# PDB.net
KiCad netlist of a schematic drawn in EAGLE
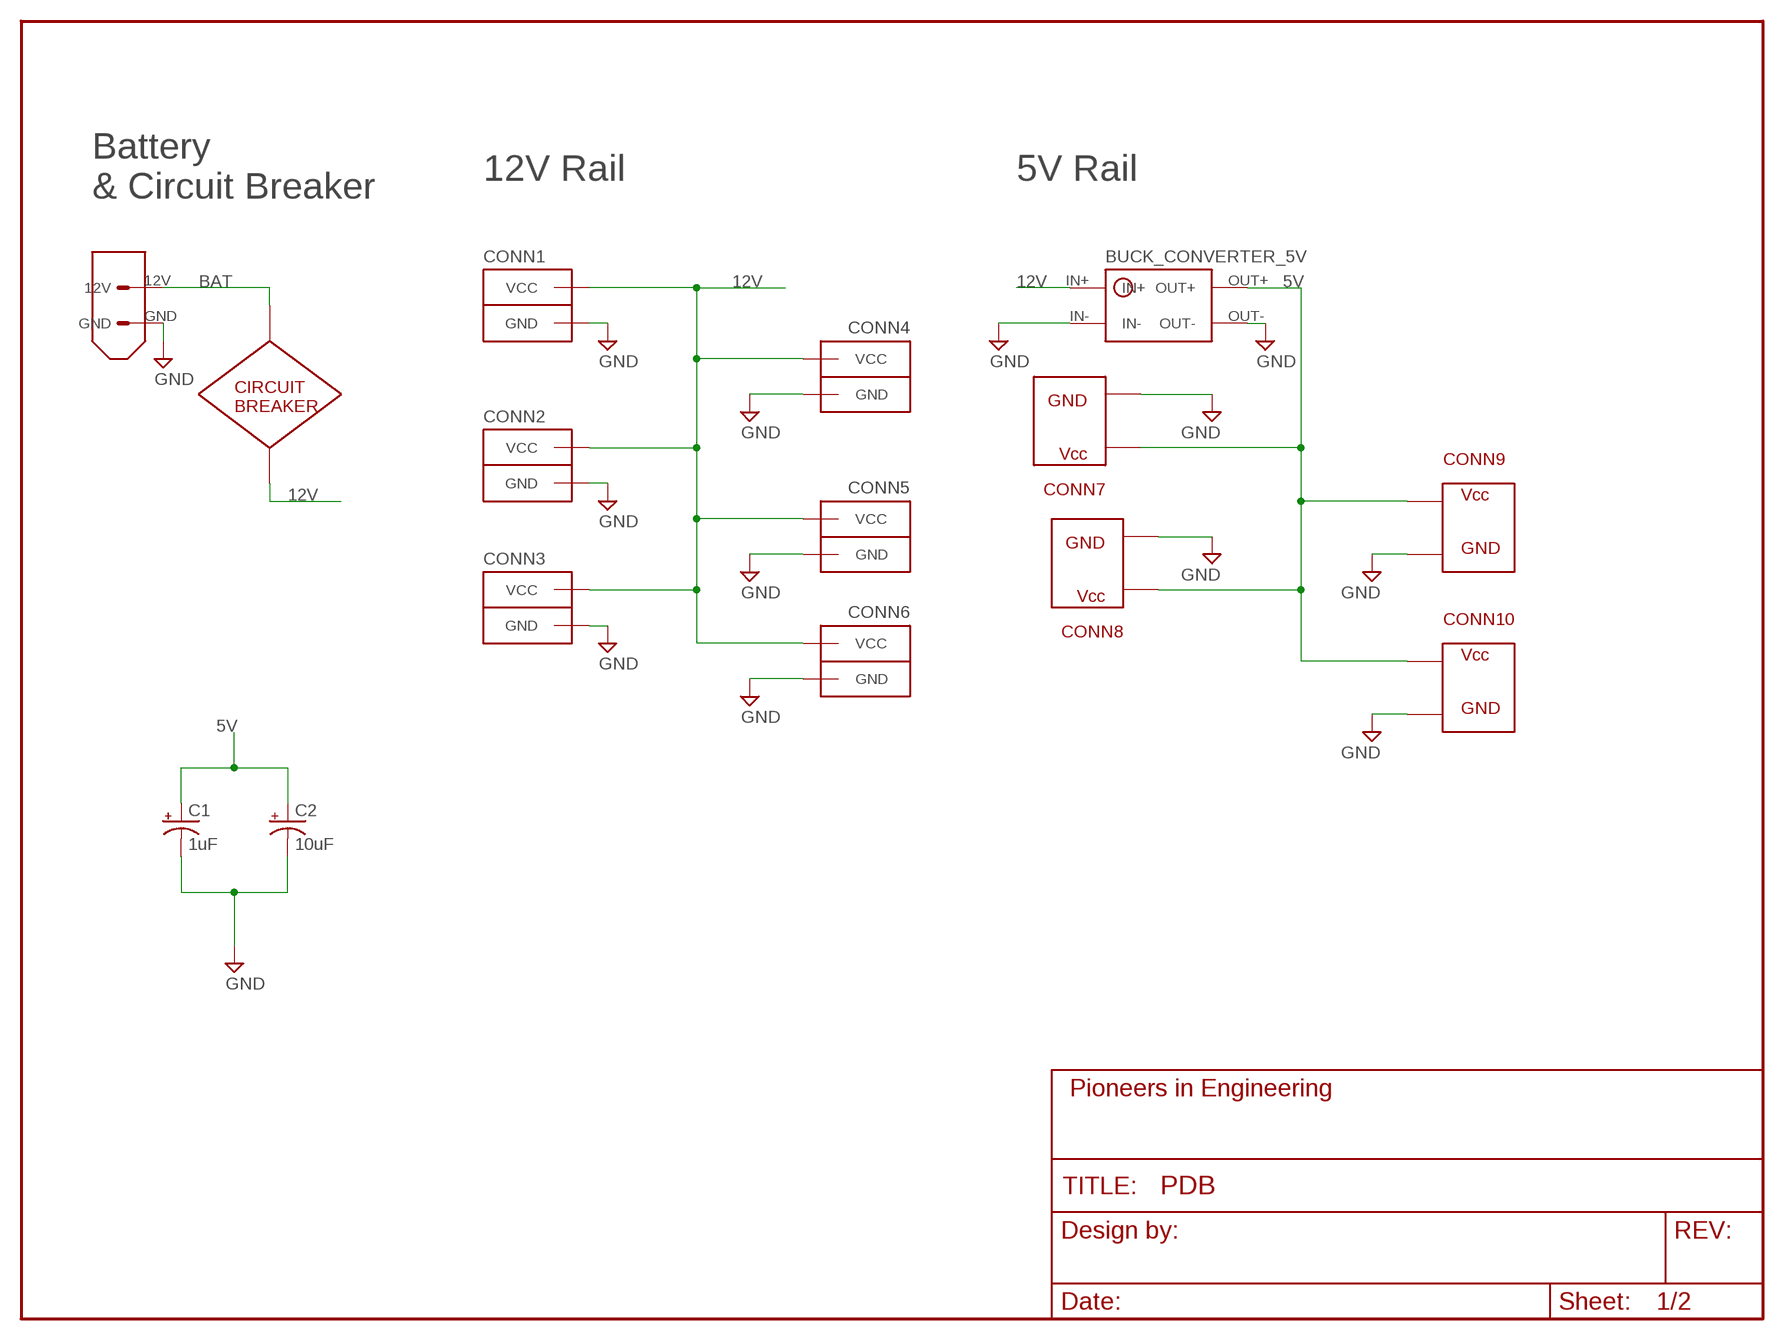
[diagram p0: schematic, sheet 1]
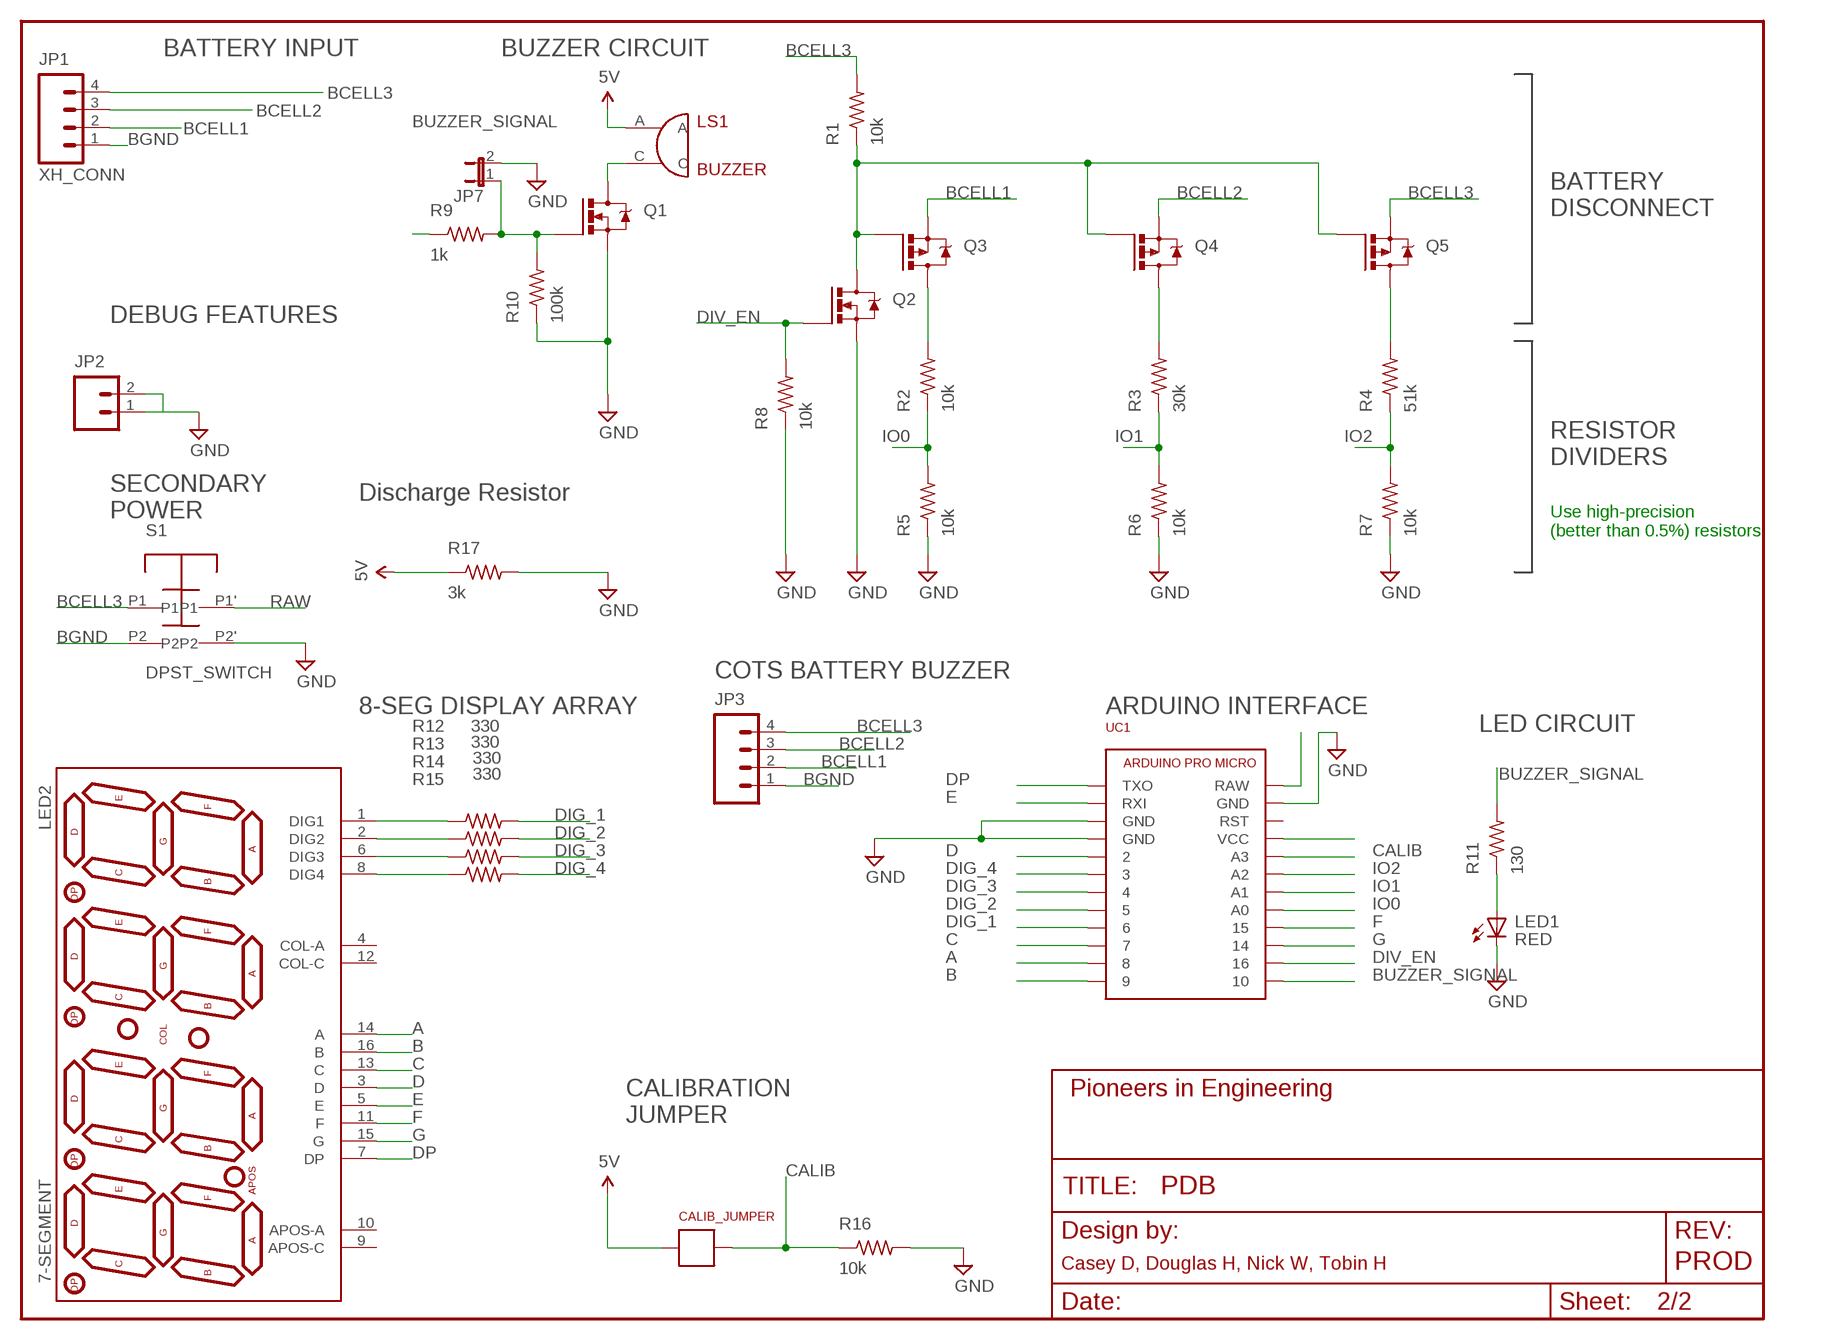
[diagram p1: schematic, sheet 2]

(export (version "E")
  (design (tool "Eeschema 10.0.6"))
  (components
    (comp (ref "CALIB_JUMPER")
      (value "JUMPER")
      (footprint "eagle-import:JUMPER")
      (fields
        (field (name "DISTRIBUTOR_PART_NUMBER") "952-2262-ND")
        (field (name "MANUFACTURER") "Harwin. Inc")
        (field (name "MANUFACTURER_PART_NUMBER") "M20-9990246")
      )
      (libsource (lib "eagle-import") (part "JUMPER"))
    )
    (comp (ref "JP1")
      (value "XH_CONN")
      (footprint "eagle-import:XH_CONNECTOR_4POS_2.5MM")
      (libsource (lib "eagle-import") (part "XH_CONNECTOR_4POS"))
    )
    (comp (ref "JP2")
      (value "M02PTH")
      (footprint "eagle-import:1X02")
      (libsource (lib "eagle-import") (part "M02PTH"))
    )
    (comp (ref "JP3")
      (value "M04PTH")
      (footprint "eagle-import:1X04")
      (libsource (lib "eagle-import") (part "M04PTH"))
    )
    (comp (ref "JP7")
      (value "JP1E")
      (footprint "eagle-import:JP1")
      (libsource (lib "eagle-import") (part "JP1E"))
    )
    (comp (ref "LED1")
      (value "RED")
      (footprint "eagle-import:LED-0805")
      (libsource (lib "eagle-import") (part "LED0805"))
    )
    (comp (ref "LED2")
      (value "7-SEGMENT")
      (footprint "eagle-import:7-SEGMENT-4DIGIT-YOUNGSUN")
      (libsource (lib "eagle-import") (part "7-SEGMENT-4DIGIT-YOUNGSUN"))
    )
    (comp (ref "LS1")
      (value "BUZZER")
      (footprint "eagle-import:BUZZER_MAGNETIC_5V_12MM_RADIAL")
      (libsource (lib "eagle-import") (part "BUZZER"))
    )
    (comp (ref "Q1")
      (value "NMOS")
      (footprint "eagle-import:SOT23-3")
      (libsource (lib "eagle-import") (part "N-CHANNEL-MOSFETSOT23-3"))
    )
    (comp (ref "Q2")
      (value "IRFML8244")
      (footprint "eagle-import:SOT23-3")
      (libsource (lib "eagle-import") (part "N-CHANNEL-MOSFETSOT23-3"))
    )
    (comp (ref "Q3")
      (value "PMOS")
      (footprint "eagle-import:SOT23-3")
      (libsource (lib "eagle-import") (part "P-CHANNEL-MOSFETSOT23-3"))
    )
    (comp (ref "Q4")
      (value "PMOS")
      (footprint "eagle-import:SOT23-3")
      (libsource (lib "eagle-import") (part "P-CHANNEL-MOSFETSOT23-3"))
    )
    (comp (ref "Q5")
      (value "PMOS")
      (footprint "eagle-import:SOT23-3")
      (libsource (lib "eagle-import") (part "P-CHANNEL-MOSFETSOT23-3"))
    )
    (comp (ref "R1")
      (value "10k")
      (footprint "eagle-import:R0603")
      (fields (field (name "MANUFACTURER") "Rohm Semiconductor"))
      (libsource (lib "eagle-import") (part "R-US_R0603"))
    )
    (comp (ref "R2")
      (value "10k")
      (footprint "eagle-import:R0603")
      (fields (field (name "MANUFACTURER") "Rohm Semiconductor"))
      (libsource (lib "eagle-import") (part "R-US_R0603"))
    )
    (comp (ref "R3")
      (value "30k")
      (footprint "eagle-import:R0603")
      (fields (field (name "MANUFACTURER") "Rohm Semiconductor"))
      (libsource (lib "eagle-import") (part "R-US_R0603"))
    )
    (comp (ref "R4")
      (value "51k")
      (footprint "eagle-import:R0603")
      (fields (field (name "MANUFACTURER") "Rohm Semiconductor"))
      (libsource (lib "eagle-import") (part "R-US_R0603"))
    )
    (comp (ref "R5")
      (value "10k")
      (footprint "eagle-import:R0603")
      (fields (field (name "MANUFACTURER") "Rohm Semiconductor"))
      (libsource (lib "eagle-import") (part "R-US_R0603"))
    )
    (comp (ref "R6")
      (value "10k")
      (footprint "eagle-import:R0603")
      (fields (field (name "MANUFACTURER") "Rohm Semiconductor"))
      (libsource (lib "eagle-import") (part "R-US_R0603"))
    )
    (comp (ref "R7")
      (value "10k")
      (footprint "eagle-import:R0603")
      (fields (field (name "MANUFACTURER") "Rohm Semiconductor"))
      (libsource (lib "eagle-import") (part "R-US_R0603"))
    )
    (comp (ref "R8")
      (value "10k")
      (footprint "eagle-import:R0603")
      (fields (field (name "MANUFACTURER") "Rohm Semiconductor"))
      (libsource (lib "eagle-import") (part "R-US_R0603"))
    )
    (comp (ref "R9")
      (value "1k")
      (footprint "eagle-import:R0603")
      (fields (field (name "MANUFACTURER") "Rohm Semiconductor"))
      (libsource (lib "eagle-import") (part "R-US_R0603"))
    )
    (comp (ref "R10")
      (value "100k")
      (footprint "eagle-import:R0603")
      (fields (field (name "MANUFACTURER") "Rohm Semiconductor"))
      (libsource (lib "eagle-import") (part "R-US_R0603"))
    )
    (comp (ref "R11")
      (value "130")
      (footprint "eagle-import:R0603")
      (fields (field (name "MANUFACTURER") "Rohm Semiconductor"))
      (libsource (lib "eagle-import") (part "R-US_R0603"))
    )
    (comp (ref "R12")
      (value "330")
      (footprint "eagle-import:R0603")
      (fields (field (name "MANUFACTURER") "Rohm Semiconductor"))
      (libsource (lib "eagle-import") (part "R-US_R0603"))
    )
    (comp (ref "R13")
      (value "330")
      (footprint "eagle-import:R0603")
      (fields (field (name "MANUFACTURER") "Rohm Semiconductor"))
      (libsource (lib "eagle-import") (part "R-US_R0603"))
    )
    (comp (ref "R14")
      (value "330")
      (footprint "eagle-import:R0603")
      (fields (field (name "MANUFACTURER") "Rohm Semiconductor"))
      (libsource (lib "eagle-import") (part "R-US_R0603"))
    )
    (comp (ref "R15")
      (value "330")
      (footprint "eagle-import:R0603")
      (fields (field (name "MANUFACTURER") "Rohm Semiconductor"))
      (libsource (lib "eagle-import") (part "R-US_R0603"))
    )
    (comp (ref "R16")
      (value "10k")
      (footprint "eagle-import:R0603")
      (fields (field (name "MANUFACTURER") "Rohm Semiconductor"))
      (libsource (lib "eagle-import") (part "R-US_R0603"))
    )
    (comp (ref "R17")
      (value "3k")
      (footprint "eagle-import:R0603")
      (fields (field (name "MANUFACTURER") "Rohm Semiconductor"))
      (libsource (lib "eagle-import") (part "R-US_R0603"))
    )
    (comp (ref "S1")
      (value "DPST_SWITCH")
      (footprint "eagle-import:C&K_SWITCH")
      (libsource (lib "eagle-import") (part "DPST_SWITCH"))
    )
    (comp (ref "UC1")
      (value "ARDUINO_PRO_MICRO")
      (footprint "eagle-import:ARDUINO_PRO_MICRO")
      (fields
        (field (name "DISTRIBUTOR_PART_NUMBER") "32284746884")
        (field (name "MANUFACTURER") "Feiyang electronics")
      )
      (libsource (lib "eagle-import") (part "ARDUINO_PRO_MICRO"))
    )
    (comp (ref "C1")
      (value "1uF")
      (footprint "eagle-import:E5-5")
      (libsource (lib "eagle-import") (part "CPOL-USE5-5"))
    )
    (comp (ref "C2")
      (value "10uF")
      (footprint "eagle-import:E5-5")
      (libsource (lib "eagle-import") (part "CPOL-USE5-5"))
    )
    (comp (ref "CIRCUIT_BREAKER")
      (value "CIRC_BREAKER")
      (footprint "eagle-import:CIRC_BREAKER")
      (libsource (lib "eagle-import") (part "CIRC_BREAKER"))
    )
    (comp (ref "CONN1")
      (value "ANDERSONVERTICAL")
      (footprint "eagle-import:ANDERSON_VERTICAL")
      (libsource (lib "eagle-import") (part "ANDERSONVERTICAL"))
    )
    (comp (ref "CONN2")
      (value "ANDERSONVERTICAL")
      (footprint "eagle-import:ANDERSON_VERTICAL")
      (libsource (lib "eagle-import") (part "ANDERSONVERTICAL"))
    )
    (comp (ref "CONN3")
      (value "ANDERSONVERTICAL")
      (footprint "eagle-import:ANDERSON_VERTICAL")
      (libsource (lib "eagle-import") (part "ANDERSONVERTICAL"))
    )
    (comp (ref "CONN4")
      (value "ANDERSONVERTICAL")
      (footprint "eagle-import:ANDERSON_VERTICAL")
      (libsource (lib "eagle-import") (part "ANDERSONVERTICAL"))
    )
    (comp (ref "CONN5")
      (value "ANDERSONVERTICAL")
      (footprint "eagle-import:ANDERSON_VERTICAL")
      (libsource (lib "eagle-import") (part "ANDERSONVERTICAL"))
    )
    (comp (ref "CONN6")
      (value "ANDERSONVERTICAL")
      (footprint "eagle-import:ANDERSON_VERTICAL")
      (libsource (lib "eagle-import") (part "ANDERSONVERTICAL"))
    )
    (comp (ref "CONN7")
      (value "ATX")
      (footprint "eagle-import:ATX")
      (libsource (lib "eagle-import") (part "ATX"))
    )
    (comp (ref "CONN8")
      (value "ATX")
      (footprint "eagle-import:ATX")
      (libsource (lib "eagle-import") (part "ATX"))
    )
    (comp (ref "CONN9")
      (value "ATX")
      (footprint "eagle-import:ATX")
      (libsource (lib "eagle-import") (part "ATX"))
    )
    (comp (ref "CONN10")
      (value "ATX")
      (footprint "eagle-import:ATX")
      (libsource (lib "eagle-import") (part "ATX"))
    )
    (comp (ref "U$1")
      (value "BUCK_CONVERTER_5V")
      (footprint "eagle-import:BUCK_CONVERTER_5V")
      (libsource (lib "eagle-import") (part "BUCK_CONVERTER_5V"))
    )
    (comp (ref "XT60")
      (value "XT60CONNECTOR")
      (footprint "eagle-import:XT60CONNECTOR")
      (fields (field (name "PARTNUMBER") "PRT-10474 "))
      (libsource (lib "eagle-import") (part "XT60CONNECTOR"))
    )
  )
  (nets
    (net (code "1") (name "5V") (class "Default")
      (node (ref "C1") (pin "+") (pinfunction "+_+") (pintype "passive"))
      (node (ref "C2") (pin "+") (pinfunction "+_+") (pintype "passive"))
      (node (ref "CALIB_JUMPER") (pin "P$1") (pinfunction "P$1_P$1") (pintype "input"))
      (node (ref "CONN10") (pin "P$1") (pinfunction "P$1_P$1") (pintype "power_in"))
      (node (ref "CONN7") (pin "P$1") (pinfunction "P$1_P$1") (pintype "power_in"))
      (node (ref "CONN8") (pin "P$1") (pinfunction "P$1_P$1") (pintype "power_in"))
      (node (ref "CONN9") (pin "P$1") (pinfunction "P$1_P$1") (pintype "power_in"))
      (node (ref "LS1") (pin "A") (pinfunction "A_A") (pintype "bidirectional"))
      (node (ref "R17") (pin "1") (pinfunction "1_1") (pintype "passive"))
      (node (ref "U$1") (pin "OUT+") (pinfunction "OUT+_OUT+") (pintype "bidirectional"))
      (node (ref "UC1") (pin "VCC") (pinfunction "VCC_VCC") (pintype "bidirectional"))
    )
    (net (code "2") (name "12V") (class "Default")
      (node (ref "CIRCUIT_BREAKER") (pin "P$2") (pinfunction "P$2_P$2") (pintype "bidirectional"))
      (node (ref "CONN1") (pin "PIN2") (pinfunction "VCC_PIN2") (pintype "bidirectional"))
      (node (ref "CONN2") (pin "PIN2") (pinfunction "VCC_PIN2") (pintype "bidirectional"))
      (node (ref "CONN3") (pin "PIN2") (pinfunction "VCC_PIN2") (pintype "bidirectional"))
      (node (ref "CONN4") (pin "PIN2") (pinfunction "VCC_PIN2") (pintype "bidirectional"))
      (node (ref "CONN5") (pin "PIN2") (pinfunction "VCC_PIN2") (pintype "bidirectional"))
      (node (ref "CONN6") (pin "PIN2") (pinfunction "VCC_PIN2") (pintype "bidirectional"))
      (node (ref "U$1") (pin "IN+") (pinfunction "IN+_IN+") (pintype "bidirectional"))
    )
    (net (code "3") (name "A") (class "Default")
      (node (ref "LED2") (pin "14") (pinfunction "A_14") (pintype "bidirectional"))
      (node (ref "UC1") (pin "8") (pinfunction "8_8") (pintype "bidirectional"))
    )
    (net (code "4") (name "B") (class "Default")
      (node (ref "LED2") (pin "16") (pinfunction "B_16") (pintype "bidirectional"))
      (node (ref "UC1") (pin "9") (pinfunction "9_9") (pintype "bidirectional"))
    )
    (net (code "5") (name "BAT") (class "Default")
      (node (ref "CIRCUIT_BREAKER") (pin "P$1") (pinfunction "P$1_P$1") (pintype "bidirectional"))
      (node (ref "XT60") (pin "12V") (pinfunction "12V_12V") (pintype "bidirectional"))
    )
    (net (code "6") (name "BCELL1") (class "Default")
      (node (ref "JP1") (pin "2") (pinfunction "2_2") (pintype "passive"))
      (node (ref "JP3") (pin "2") (pinfunction "2_2") (pintype "passive"))
      (node (ref "Q3") (pin "2") (pinfunction "S_2") (pintype "passive"))
    )
    (net (code "7") (name "BCELL2") (class "Default")
      (node (ref "JP1") (pin "3") (pinfunction "3_3") (pintype "passive"))
      (node (ref "JP3") (pin "3") (pinfunction "3_3") (pintype "passive"))
      (node (ref "Q4") (pin "2") (pinfunction "S_2") (pintype "passive"))
    )
    (net (code "8") (name "BCELL3") (class "Default")
      (node (ref "JP1") (pin "4") (pinfunction "4_4") (pintype "passive"))
      (node (ref "JP3") (pin "4") (pinfunction "4_4") (pintype "passive"))
      (node (ref "Q5") (pin "2") (pinfunction "S_2") (pintype "passive"))
      (node (ref "R1") (pin "2") (pinfunction "2_2") (pintype "passive"))
      (node (ref "S1") (pin "P1") (pinfunction "P1_P1") (pintype "bidirectional"))
    )
    (net (code "9") (name "BGND") (class "Default")
      (node (ref "JP1") (pin "1") (pinfunction "1_1") (pintype "passive"))
      (node (ref "JP3") (pin "1") (pinfunction "1_1") (pintype "passive"))
      (node (ref "S1") (pin "P2") (pinfunction "P2_P2") (pintype "bidirectional"))
    )
    (net (code "10") (name "BUZZER_SIGNAL") (class "Default")
      (node (ref "R11") (pin "2") (pinfunction "2_2") (pintype "passive"))
      (node (ref "R9") (pin "1") (pinfunction "1_1") (pintype "passive"))
      (node (ref "UC1") (pin "10") (pinfunction "10_10") (pintype "bidirectional"))
    )
    (net (code "11") (name "C") (class "Default")
      (node (ref "LED2") (pin "13") (pinfunction "C_13") (pintype "bidirectional"))
      (node (ref "UC1") (pin "7") (pinfunction "7_7") (pintype "bidirectional"))
    )
    (net (code "12") (name "CALIB") (class "Default")
      (node (ref "CALIB_JUMPER") (pin "P$2") (pinfunction "P$2_P$2") (pintype "bidirectional"))
      (node (ref "R16") (pin "1") (pinfunction "1_1") (pintype "passive"))
      (node (ref "UC1") (pin "A3") (pinfunction "A3_A3") (pintype "bidirectional"))
    )
    (net (code "13") (name "D") (class "Default")
      (node (ref "LED2") (pin "3") (pinfunction "D_3") (pintype "bidirectional"))
      (node (ref "UC1") (pin "2") (pinfunction "2_2") (pintype "bidirectional"))
    )
    (net (code "14") (name "DIG_1") (class "Default")
      (node (ref "R12") (pin "2") (pinfunction "2_2") (pintype "passive"))
      (node (ref "UC1") (pin "6") (pinfunction "6_6") (pintype "bidirectional"))
    )
    (net (code "15") (name "DIG_2") (class "Default")
      (node (ref "R13") (pin "2") (pinfunction "2_2") (pintype "passive"))
      (node (ref "UC1") (pin "5") (pinfunction "5_5") (pintype "bidirectional"))
    )
    (net (code "16") (name "DIG_3") (class "Default")
      (node (ref "R14") (pin "2") (pinfunction "2_2") (pintype "passive"))
      (node (ref "UC1") (pin "4") (pinfunction "4_4") (pintype "bidirectional"))
    )
    (net (code "17") (name "DIG_4") (class "Default")
      (node (ref "R15") (pin "2") (pinfunction "2_2") (pintype "passive"))
      (node (ref "UC1") (pin "3") (pinfunction "3_3") (pintype "bidirectional"))
    )
    (net (code "18") (name "DIV_EN") (class "Default")
      (node (ref "Q2") (pin "1") (pinfunction "G_1") (pintype "passive"))
      (node (ref "R8") (pin "2") (pinfunction "2_2") (pintype "passive"))
      (node (ref "UC1") (pin "16") (pinfunction "16_16") (pintype "bidirectional"))
    )
    (net (code "19") (name "DP") (class "Default")
      (node (ref "LED2") (pin "7") (pinfunction "DP_7") (pintype "bidirectional"))
      (node (ref "UC1") (pin "TXO") (pinfunction "TXO_TXO") (pintype "bidirectional"))
    )
    (net (code "20") (name "E") (class "Default")
      (node (ref "LED2") (pin "5") (pinfunction "E_5") (pintype "bidirectional"))
      (node (ref "UC1") (pin "RXI") (pinfunction "RXI_RXI") (pintype "bidirectional"))
    )
    (net (code "21") (name "F") (class "Default")
      (node (ref "LED2") (pin "11") (pinfunction "F_11") (pintype "bidirectional"))
      (node (ref "UC1") (pin "15") (pinfunction "15_15") (pintype "bidirectional"))
    )
    (net (code "22") (name "G") (class "Default")
      (node (ref "LED2") (pin "15") (pinfunction "G_15") (pintype "bidirectional"))
      (node (ref "UC1") (pin "14") (pinfunction "14_14") (pintype "bidirectional"))
    )
    (net (code "23") (name "GND") (class "Default")
      (node (ref "C1") (pin "-") (pinfunction "-_-") (pintype "passive"))
      (node (ref "C2") (pin "-") (pinfunction "-_-") (pintype "passive"))
      (node (ref "CONN1") (pin "PIN1") (pinfunction "GND_PIN1") (pintype "bidirectional"))
      (node (ref "CONN10") (pin "P$2") (pinfunction "P$2_P$2") (pintype "power_in"))
      (node (ref "CONN2") (pin "PIN1") (pinfunction "GND_PIN1") (pintype "bidirectional"))
      (node (ref "CONN3") (pin "PIN1") (pinfunction "GND_PIN1") (pintype "bidirectional"))
      (node (ref "CONN4") (pin "PIN1") (pinfunction "GND_PIN1") (pintype "bidirectional"))
      (node (ref "CONN5") (pin "PIN1") (pinfunction "GND_PIN1") (pintype "bidirectional"))
      (node (ref "CONN6") (pin "PIN1") (pinfunction "GND_PIN1") (pintype "bidirectional"))
      (node (ref "CONN7") (pin "P$2") (pinfunction "P$2_P$2") (pintype "power_in"))
      (node (ref "CONN8") (pin "P$2") (pinfunction "P$2_P$2") (pintype "power_in"))
      (node (ref "CONN9") (pin "P$2") (pinfunction "P$2_P$2") (pintype "power_in"))
      (node (ref "JP2") (pin "1") (pinfunction "1_1") (pintype "passive"))
      (node (ref "JP2") (pin "2") (pinfunction "2_2") (pintype "passive"))
      (node (ref "JP7") (pin "2") (pinfunction "2_2") (pintype "passive"))
      (node (ref "LED1") (pin "C") (pinfunction "C_C") (pintype "passive"))
      (node (ref "Q1") (pin "2") (pinfunction "S_2") (pintype "passive"))
      (node (ref "Q2") (pin "2") (pinfunction "S_2") (pintype "passive"))
      (node (ref "R10") (pin "1") (pinfunction "1_1") (pintype "passive"))
      (node (ref "R16") (pin "2") (pinfunction "2_2") (pintype "passive"))
      (node (ref "R17") (pin "2") (pinfunction "2_2") (pintype "passive"))
      (node (ref "R5") (pin "1") (pinfunction "1_1") (pintype "passive"))
      (node (ref "R6") (pin "1") (pinfunction "1_1") (pintype "passive"))
      (node (ref "R7") (pin "1") (pinfunction "1_1") (pintype "passive"))
      (node (ref "R8") (pin "1") (pinfunction "1_1") (pintype "passive"))
      (node (ref "S1") (pin "P2'") (pinfunction "P2'_P2'") (pintype "bidirectional"))
      (node (ref "U$1") (pin "IN-") (pinfunction "IN-_IN-") (pintype "bidirectional"))
      (node (ref "U$1") (pin "OUT-") (pinfunction "OUT-_OUT-") (pintype "bidirectional"))
      (node (ref "UC1") (pin "GND@0") (pinfunction "GND_GND@0") (pintype "bidirectional"))
      (node (ref "UC1") (pin "GND@1") (pinfunction "GND_GND@1") (pintype "bidirectional"))
      (node (ref "UC1") (pin "GND@2") (pinfunction "GND_GND@2") (pintype "bidirectional"))
      (node (ref "XT60") (pin "GND") (pinfunction "GND_GND") (pintype "bidirectional"))
    )
    (net (code "24") (name "IO0") (class "Default")
      (node (ref "R2") (pin "1") (pinfunction "1_1") (pintype "passive"))
      (node (ref "R5") (pin "2") (pinfunction "2_2") (pintype "passive"))
      (node (ref "UC1") (pin "A0") (pinfunction "A0_A0") (pintype "bidirectional"))
    )
    (net (code "25") (name "IO1") (class "Default")
      (node (ref "R3") (pin "1") (pinfunction "1_1") (pintype "passive"))
      (node (ref "R6") (pin "2") (pinfunction "2_2") (pintype "passive"))
      (node (ref "UC1") (pin "A1") (pinfunction "A1_A1") (pintype "bidirectional"))
    )
    (net (code "26") (name "IO2") (class "Default")
      (node (ref "R4") (pin "1") (pinfunction "1_1") (pintype "passive"))
      (node (ref "R7") (pin "2") (pinfunction "2_2") (pintype "passive"))
      (node (ref "UC1") (pin "A2") (pinfunction "A2_A2") (pintype "bidirectional"))
    )
    (net (code "27") (name "Net-(LED1-PadA)") (class "Default")
      (node (ref "LED1") (pin "A") (pinfunction "A_A") (pintype "passive"))
      (node (ref "R11") (pin "1") (pinfunction "1_1") (pintype "passive"))
    )
    (net (code "28") (name "Net-(LED2-DIG1)") (class "Default")
      (node (ref "LED2") (pin "1") (pinfunction "DIG1_1") (pintype "bidirectional"))
      (node (ref "R12") (pin "1") (pinfunction "1_1") (pintype "passive"))
    )
    (net (code "29") (name "Net-(LED2-DIG2)") (class "Default")
      (node (ref "LED2") (pin "2") (pinfunction "DIG2_2") (pintype "bidirectional"))
      (node (ref "R13") (pin "1") (pinfunction "1_1") (pintype "passive"))
    )
    (net (code "30") (name "Net-(LED2-DIG3)") (class "Default")
      (node (ref "LED2") (pin "6") (pinfunction "DIG3_6") (pintype "bidirectional"))
      (node (ref "R14") (pin "1") (pinfunction "1_1") (pintype "passive"))
    )
    (net (code "31") (name "Net-(LED2-DIG4)") (class "Default")
      (node (ref "LED2") (pin "8") (pinfunction "DIG4_8") (pintype "bidirectional"))
      (node (ref "R15") (pin "1") (pinfunction "1_1") (pintype "passive"))
    )
    (net (code "32") (name "Net-(Q1-D)") (class "Default")
      (node (ref "LS1") (pin "C") (pinfunction "C_C") (pintype "bidirectional"))
      (node (ref "Q1") (pin "3") (pinfunction "D_3") (pintype "passive"))
    )
    (net (code "33") (name "Net-(Q1-G)") (class "Default")
      (node (ref "JP7") (pin "1") (pinfunction "1_1") (pintype "passive"))
      (node (ref "Q1") (pin "1") (pinfunction "G_1") (pintype "passive"))
      (node (ref "R10") (pin "2") (pinfunction "2_2") (pintype "passive"))
      (node (ref "R9") (pin "2") (pinfunction "2_2") (pintype "passive"))
    )
    (net (code "34") (name "Net-(Q2-D)") (class "Default")
      (node (ref "Q2") (pin "3") (pinfunction "D_3") (pintype "passive"))
      (node (ref "Q3") (pin "1") (pinfunction "G_1") (pintype "passive"))
      (node (ref "Q4") (pin "1") (pinfunction "G_1") (pintype "passive"))
      (node (ref "Q5") (pin "1") (pinfunction "G_1") (pintype "passive"))
      (node (ref "R1") (pin "1") (pinfunction "1_1") (pintype "passive"))
    )
    (net (code "35") (name "Net-(Q3-D)") (class "Default")
      (node (ref "Q3") (pin "3") (pinfunction "D_3") (pintype "passive"))
      (node (ref "R2") (pin "2") (pinfunction "2_2") (pintype "passive"))
    )
    (net (code "36") (name "Net-(Q4-D)") (class "Default")
      (node (ref "Q4") (pin "3") (pinfunction "D_3") (pintype "passive"))
      (node (ref "R3") (pin "2") (pinfunction "2_2") (pintype "passive"))
    )
    (net (code "37") (name "Net-(Q5-D)") (class "Default")
      (node (ref "Q5") (pin "3") (pinfunction "D_3") (pintype "passive"))
      (node (ref "R4") (pin "2") (pinfunction "2_2") (pintype "passive"))
    )
    (net (code "38") (name "RAW") (class "Default")
      (node (ref "S1") (pin "P1'") (pinfunction "P1'_P1'") (pintype "bidirectional"))
      (node (ref "UC1") (pin "RAW") (pinfunction "RAW_RAW") (pintype "bidirectional"))
    )
    (net (code "39") (name "unconnected-(LED2-APOS-A-Pad10)") (class "Default")
      (node (ref "LED2") (pin "10") (pinfunction "APOS-A_10") (pintype "bidirectional"))
    )
    (net (code "40") (name "unconnected-(LED2-APOS-C-Pad9)") (class "Default")
      (node (ref "LED2") (pin "9") (pinfunction "APOS-C_9") (pintype "bidirectional"))
    )
    (net (code "41") (name "unconnected-(LED2-COL-A-Pad4)") (class "Default")
      (node (ref "LED2") (pin "4") (pinfunction "COL-A_4") (pintype "bidirectional"))
    )
    (net (code "42") (name "unconnected-(LED2-COL-C-Pad12)") (class "Default")
      (node (ref "LED2") (pin "12") (pinfunction "COL-C_12") (pintype "bidirectional"))
    )
    (net (code "43") (name "unconnected-(UC1-PadRST)") (class "Default")
      (node (ref "UC1") (pin "RST") (pinfunction "RST_RST") (pintype "bidirectional"))
    )
  )
)
